# PowerSupply.net
KiCad netlist of a schematic drawn in Altium Designer
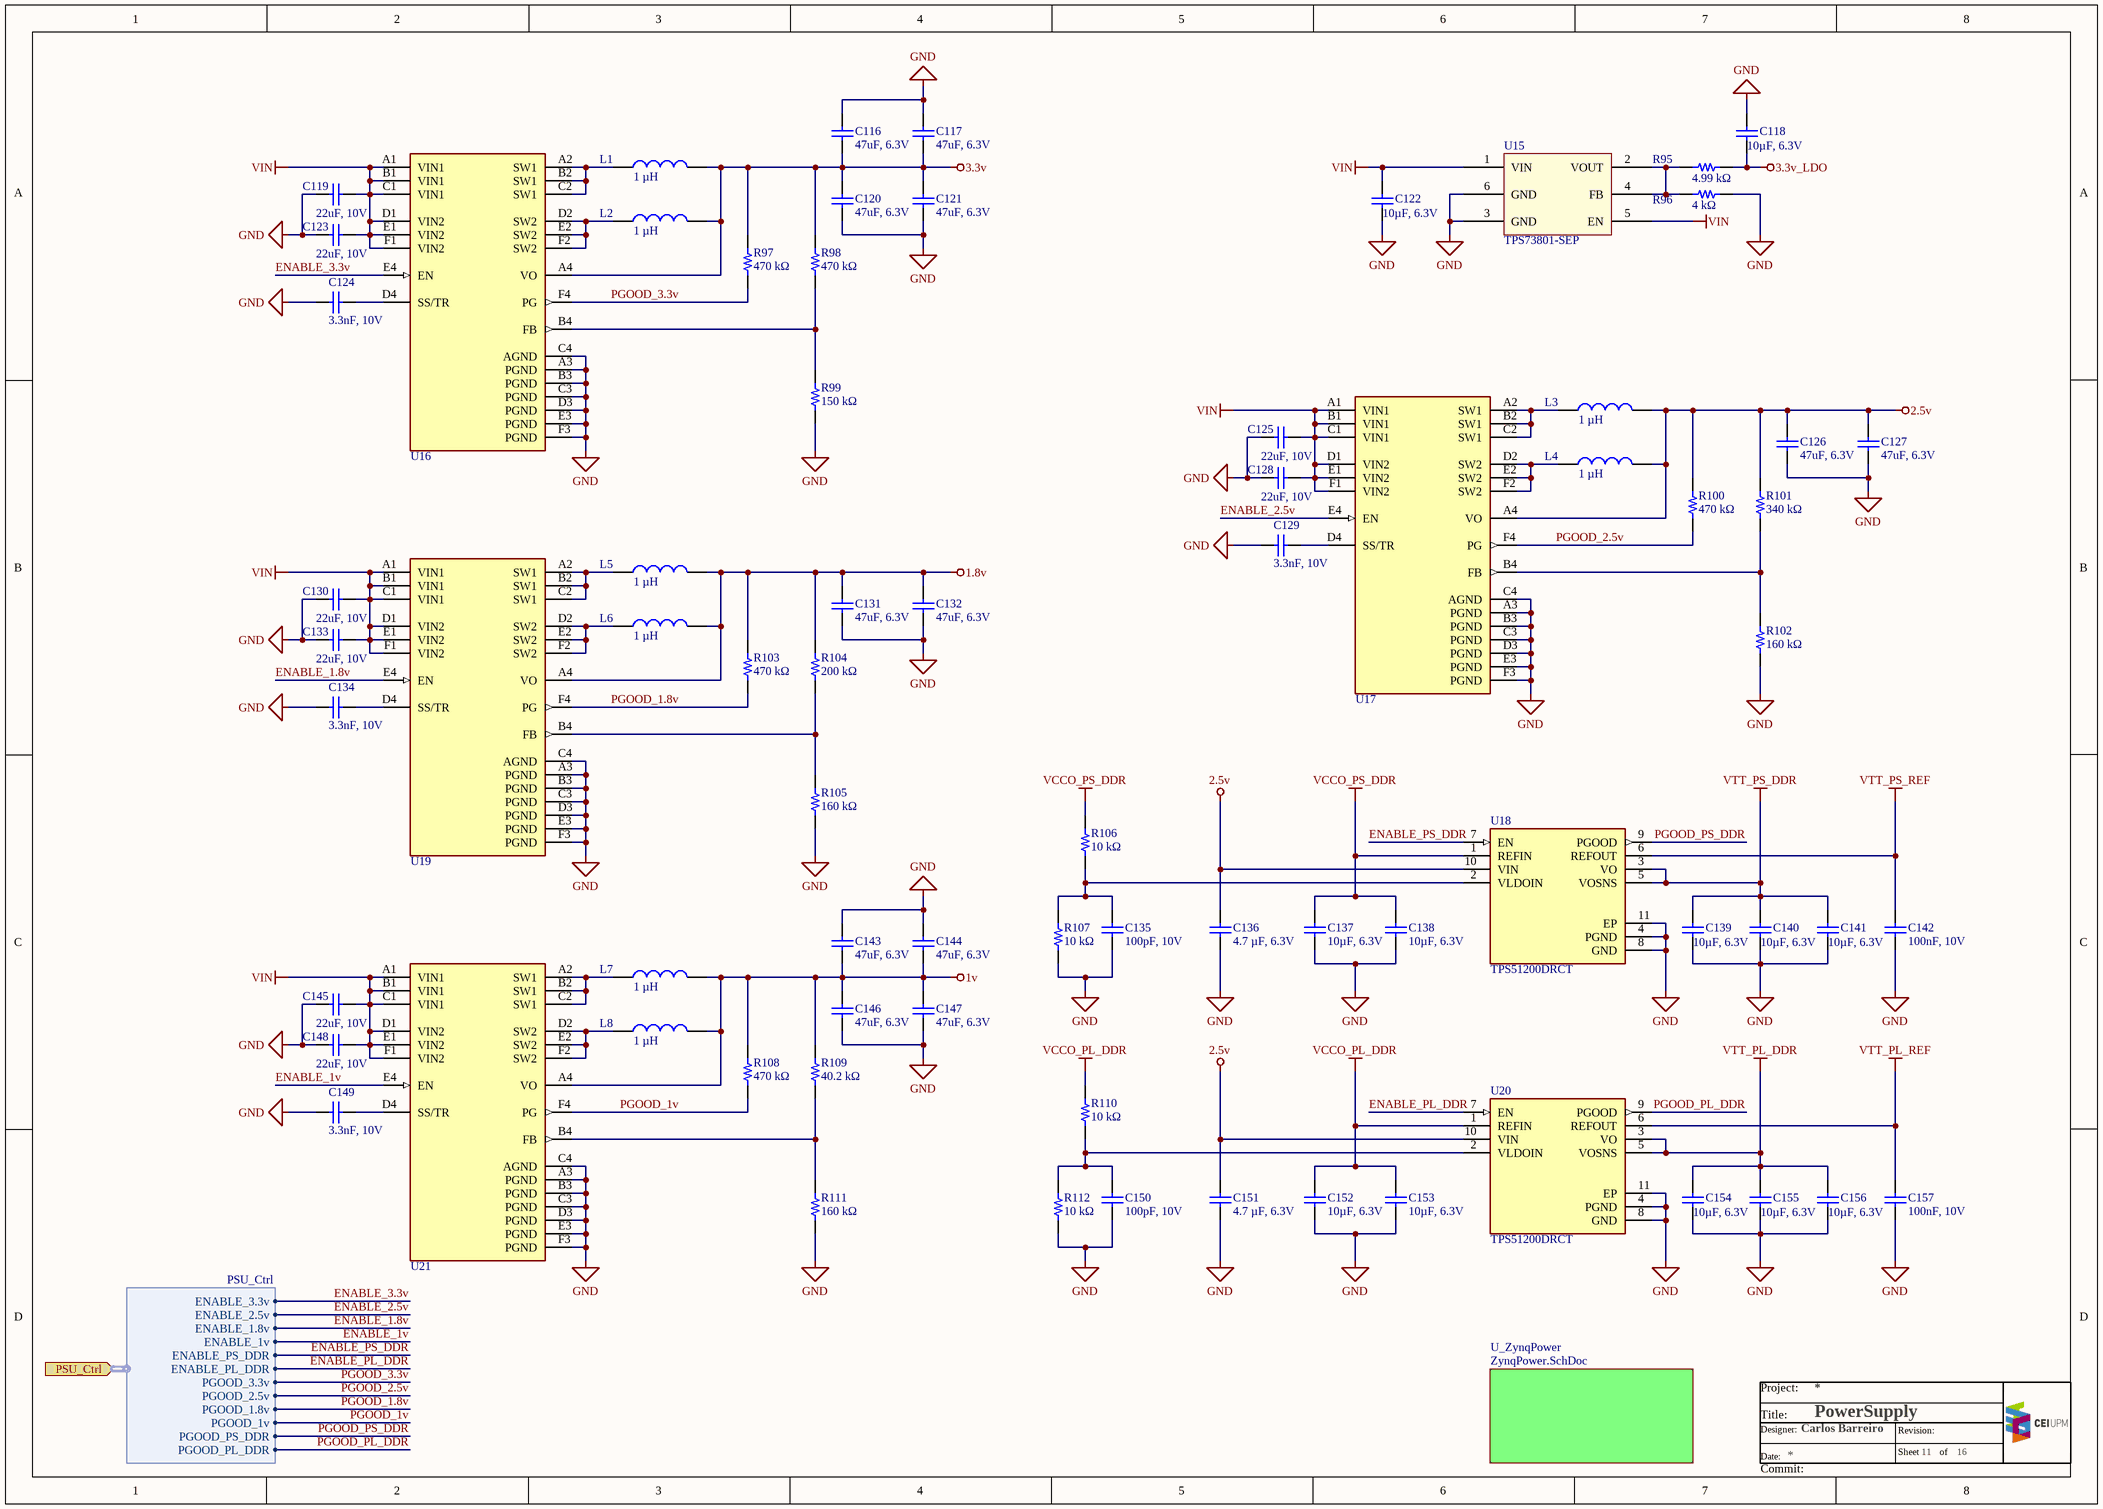
[diagram p0: PowerSupply.SchDoc]

(export (version "E")
  (design (tool "Eeschema 10.0.6"))
  (components
    (comp (ref "C116")
      (value "47uF, 6.3V")
      (footprint "WURTH_WCAP-CSGP_0805_H=1.25mm")
      (description "WCAP-CSGP Multilayer Ceramic Chip Capacitor, General Purpose, size 0805, X5R, 47uF, 6.3V")
      (fields
        (field (name "MANUFACTURER PART NUMBER") "885012107006")
        (field (name "MANUFACTURER") "Wurth Elektronik")
      )
      (libsource (lib "SpaceVNX") (part "885012107006"))
    )
    (comp (ref "C117")
      (value "47uF, 6.3V")
      (footprint "WURTH_WCAP-CSGP_0805_H=1.25mm")
      (description "WCAP-CSGP Multilayer Ceramic Chip Capacitor, General Purpose, size 0805, X5R, 47uF, 6.3V")
      (fields
        (field (name "MANUFACTURER PART NUMBER") "885012107006")
        (field (name "MANUFACTURER") "Wurth Elektronik")
      )
      (libsource (lib "SpaceVNX") (part "885012107006"))
    )
    (comp (ref "C118")
      (value "10µF, 6.3V")
      (footprint "WURTH_WCAP-CSGP_0402")
      (description "WCAP-CSGP Multilayer Ceramic Chip Capacitor, General Purpose, size 0402, X5R, 10uF, 6.3V")
      (fields
        (field (name "MANUFACTURER PART NUMBER") "885012105020")
        (field (name "MANUFACTURER") "Wurth Elektronik")
      )
      (libsource (lib "SpaceVNX") (part "885012105020"))
    )
    (comp (ref "C119")
      (value "22uF, 10V")
      (footprint "WURTH_WCAP-CSGP_0805_H=1.25mm")
      (description "WCAP-CSGP Multilayer Ceramic Chip Capacitor, General Purpose, size 0805, X5R, 22uF, 10V")
      (fields
        (field (name "MANUFACTURER PART NUMBER") "885012107011")
        (field (name "MANUFACTURER") "Wurth Elektronik")
      )
      (libsource (lib "SpaceVNX") (part "885012107011"))
    )
    (comp (ref "C120")
      (value "47uF, 6.3V")
      (footprint "WURTH_WCAP-CSGP_0805_H=1.25mm")
      (description "WCAP-CSGP Multilayer Ceramic Chip Capacitor, General Purpose, size 0805, X5R, 47uF, 6.3V")
      (fields
        (field (name "MANUFACTURER PART NUMBER") "885012107006")
        (field (name "MANUFACTURER") "Wurth Elektronik")
      )
      (libsource (lib "SpaceVNX") (part "885012107006"))
    )
    (comp (ref "C121")
      (value "47uF, 6.3V")
      (footprint "WURTH_WCAP-CSGP_0805_H=1.25mm")
      (description "WCAP-CSGP Multilayer Ceramic Chip Capacitor, General Purpose, size 0805, X5R, 47uF, 6.3V")
      (fields
        (field (name "MANUFACTURER PART NUMBER") "885012107006")
        (field (name "MANUFACTURER") "Wurth Elektronik")
      )
      (libsource (lib "SpaceVNX") (part "885012107006"))
    )
    (comp (ref "C122")
      (value "10µF, 6.3V")
      (footprint "WURTH_WCAP-CSGP_0402")
      (description "WCAP-CSGP Multilayer Ceramic Chip Capacitor, General Purpose, size 0402, X5R, 10uF, 6.3V")
      (fields
        (field (name "MANUFACTURER PART NUMBER") "885012105020")
        (field (name "MANUFACTURER") "Wurth Elektronik")
      )
      (libsource (lib "SpaceVNX") (part "885012105020"))
    )
    (comp (ref "C123")
      (value "22uF, 10V")
      (footprint "WURTH_WCAP-CSGP_0805_H=1.25mm")
      (description "WCAP-CSGP Multilayer Ceramic Chip Capacitor, General Purpose, size 0805, X5R, 22uF, 10V")
      (fields
        (field (name "MANUFACTURER PART NUMBER") "885012107011")
        (field (name "MANUFACTURER") "Wurth Elektronik")
      )
      (libsource (lib "SpaceVNX") (part "885012107011"))
    )
    (comp (ref "C124")
      (value "3.3nF, 10V")
      (footprint "WURTH_WCAP-CSGP_0402")
      (description "WCAP-CSGP Multilayer Ceramic Chip Capacitor, General Purpose, size 0402, X7R, 3.3nF, 10V")
      (fields
        (field (name "MANUFACTURER PART NUMBER") "885012205009")
        (field (name "MANUFACTURER") "Wurth Elektronik")
      )
      (libsource (lib "SpaceVNX") (part "885012205009"))
    )
    (comp (ref "C125")
      (value "22uF, 10V")
      (footprint "WURTH_WCAP-CSGP_0805_H=1.25mm")
      (description "WCAP-CSGP Multilayer Ceramic Chip Capacitor, General Purpose, size 0805, X5R, 22uF, 10V")
      (fields
        (field (name "MANUFACTURER PART NUMBER") "885012107011")
        (field (name "MANUFACTURER") "Wurth Elektronik")
      )
      (libsource (lib "SpaceVNX") (part "885012107011"))
    )
    (comp (ref "C126")
      (value "47uF, 6.3V")
      (footprint "WURTH_WCAP-CSGP_0805_H=1.25mm")
      (description "WCAP-CSGP Multilayer Ceramic Chip Capacitor, General Purpose, size 0805, X5R, 47uF, 6.3V")
      (fields
        (field (name "MANUFACTURER PART NUMBER") "885012107006")
        (field (name "MANUFACTURER") "Wurth Elektronik")
      )
      (libsource (lib "SpaceVNX") (part "885012107006"))
    )
    (comp (ref "C127")
      (value "47uF, 6.3V")
      (footprint "WURTH_WCAP-CSGP_0805_H=1.25mm")
      (description "WCAP-CSGP Multilayer Ceramic Chip Capacitor, General Purpose, size 0805, X5R, 47uF, 6.3V")
      (fields
        (field (name "MANUFACTURER PART NUMBER") "885012107006")
        (field (name "MANUFACTURER") "Wurth Elektronik")
      )
      (libsource (lib "SpaceVNX") (part "885012107006"))
    )
    (comp (ref "C128")
      (value "22uF, 10V")
      (footprint "WURTH_WCAP-CSGP_0805_H=1.25mm")
      (description "WCAP-CSGP Multilayer Ceramic Chip Capacitor, General Purpose, size 0805, X5R, 22uF, 10V")
      (fields
        (field (name "MANUFACTURER PART NUMBER") "885012107011")
        (field (name "MANUFACTURER") "Wurth Elektronik")
      )
      (libsource (lib "SpaceVNX") (part "885012107011"))
    )
    (comp (ref "C129")
      (value "3.3nF, 10V")
      (footprint "WURTH_WCAP-CSGP_0402")
      (description "WCAP-CSGP Multilayer Ceramic Chip Capacitor, General Purpose, size 0402, X7R, 3.3nF, 10V")
      (fields
        (field (name "MANUFACTURER PART NUMBER") "885012205009")
        (field (name "MANUFACTURER") "Wurth Elektronik")
      )
      (libsource (lib "SpaceVNX") (part "885012205009"))
    )
    (comp (ref "C130")
      (value "22uF, 10V")
      (footprint "WURTH_WCAP-CSGP_0805_H=1.25mm")
      (description "WCAP-CSGP Multilayer Ceramic Chip Capacitor, General Purpose, size 0805, X5R, 22uF, 10V")
      (fields
        (field (name "MANUFACTURER PART NUMBER") "885012107011")
        (field (name "MANUFACTURER") "Wurth Elektronik")
      )
      (libsource (lib "SpaceVNX") (part "885012107011"))
    )
    (comp (ref "C131")
      (value "47uF, 6.3V")
      (footprint "WURTH_WCAP-CSGP_0805_H=1.25mm")
      (description "WCAP-CSGP Multilayer Ceramic Chip Capacitor, General Purpose, size 0805, X5R, 47uF, 6.3V")
      (fields
        (field (name "MANUFACTURER PART NUMBER") "885012107006")
        (field (name "MANUFACTURER") "Wurth Elektronik")
      )
      (libsource (lib "SpaceVNX") (part "885012107006"))
    )
    (comp (ref "C132")
      (value "47uF, 6.3V")
      (footprint "WURTH_WCAP-CSGP_0805_H=1.25mm")
      (description "WCAP-CSGP Multilayer Ceramic Chip Capacitor, General Purpose, size 0805, X5R, 47uF, 6.3V")
      (fields
        (field (name "MANUFACTURER PART NUMBER") "885012107006")
        (field (name "MANUFACTURER") "Wurth Elektronik")
      )
      (libsource (lib "SpaceVNX") (part "885012107006"))
    )
    (comp (ref "C133")
      (value "22uF, 10V")
      (footprint "WURTH_WCAP-CSGP_0805_H=1.25mm")
      (description "WCAP-CSGP Multilayer Ceramic Chip Capacitor, General Purpose, size 0805, X5R, 22uF, 10V")
      (fields
        (field (name "MANUFACTURER PART NUMBER") "885012107011")
        (field (name "MANUFACTURER") "Wurth Elektronik")
      )
      (libsource (lib "SpaceVNX") (part "885012107011"))
    )
    (comp (ref "C134")
      (value "3.3nF, 10V")
      (footprint "WURTH_WCAP-CSGP_0402")
      (description "WCAP-CSGP Multilayer Ceramic Chip Capacitor, General Purpose, size 0402, X7R, 3.3nF, 10V")
      (fields
        (field (name "MANUFACTURER PART NUMBER") "885012205009")
        (field (name "MANUFACTURER") "Wurth Elektronik")
      )
      (libsource (lib "SpaceVNX") (part "885012205009"))
    )
    (comp (ref "C135")
      (value "100pF, 10V")
      (footprint "WURTH_WCAP-CSGP_0402")
      (description "WCAP-CSGP Multilayer Ceramic Chip Capacitor, General Purpose, size 0402, NP0, 100pF, 10V")
      (fields
        (field (name "MANUFACTURER PART NUMBER") "885012005013")
        (field (name "MANUFACTURER") "Wurth Elektronik")
      )
      (libsource (lib "SpaceVNX") (part "885012005013"))
    )
    (comp (ref "C136")
      (value "4.7 µF, 6.3V")
      (footprint "WURTH_WCAP-CSGP_0402")
      (description "Multilayer Ceramic Capacitors MLCC, size 0402, X5R, 4.7 µF, 6.3V")
      (fields
        (field (name "MANUFACTURER PART NUMBER") "GRM155C80J475MEAAD")
        (field (name "MANUFACTURER") "Murata")
      )
      (libsource (lib "SpaceVNX") (part "GRM155C80J475MEAAD"))
    )
    (comp (ref "C137")
      (value "10µF, 6.3V")
      (footprint "WURTH_WCAP-CSGP_0402")
      (description "WCAP-CSGP Multilayer Ceramic Chip Capacitor, General Purpose, size 0402, X5R, 10uF, 6.3V")
      (fields
        (field (name "MANUFACTURER PART NUMBER") "885012105020")
        (field (name "MANUFACTURER") "Wurth Elektronik")
      )
      (libsource (lib "SpaceVNX") (part "885012105020"))
    )
    (comp (ref "C138")
      (value "10µF, 6.3V")
      (footprint "WURTH_WCAP-CSGP_0402")
      (description "WCAP-CSGP Multilayer Ceramic Chip Capacitor, General Purpose, size 0402, X5R, 10uF, 6.3V")
      (fields
        (field (name "MANUFACTURER PART NUMBER") "885012105020")
        (field (name "MANUFACTURER") "Wurth Elektronik")
      )
      (libsource (lib "SpaceVNX") (part "885012105020"))
    )
    (comp (ref "C139")
      (value "10µF, 6.3V")
      (footprint "WURTH_WCAP-CSGP_0402")
      (description "WCAP-CSGP Multilayer Ceramic Chip Capacitor, General Purpose, size 0402, X5R, 10uF, 6.3V")
      (fields
        (field (name "MANUFACTURER PART NUMBER") "885012105020")
        (field (name "MANUFACTURER") "Wurth Elektronik")
      )
      (libsource (lib "SpaceVNX") (part "885012105020"))
    )
    (comp (ref "C140")
      (value "10µF, 6.3V")
      (footprint "WURTH_WCAP-CSGP_0402")
      (description "WCAP-CSGP Multilayer Ceramic Chip Capacitor, General Purpose, size 0402, X5R, 10uF, 6.3V")
      (fields
        (field (name "MANUFACTURER PART NUMBER") "885012105020")
        (field (name "MANUFACTURER") "Wurth Elektronik")
      )
      (libsource (lib "SpaceVNX") (part "885012105020"))
    )
    (comp (ref "C141")
      (value "10µF, 6.3V")
      (footprint "WURTH_WCAP-CSGP_0402")
      (description "WCAP-CSGP Multilayer Ceramic Chip Capacitor, General Purpose, size 0402, X5R, 10uF, 6.3V")
      (fields
        (field (name "MANUFACTURER PART NUMBER") "885012105020")
        (field (name "MANUFACTURER") "Wurth Elektronik")
      )
      (libsource (lib "SpaceVNX") (part "885012105020"))
    )
    (comp (ref "C142")
      (value "100nF, 10V")
      (footprint "WURTH_WCAP-CSGP_0402")
      (description "WCAP-CSGP Multilayer Ceramic Chip Capacitor, General Purpose, size 0402, X7R, 100nF, 10V")
      (fields
        (field (name "MANUFACTURER PART NUMBER") "885012205018")
        (field (name "MANUFACTURER") "Wurth Elektronik")
      )
      (libsource (lib "SpaceVNX") (part "885012205018"))
    )
    (comp (ref "C143")
      (value "47uF, 6.3V")
      (footprint "WURTH_WCAP-CSGP_0805_H=1.25mm")
      (description "WCAP-CSGP Multilayer Ceramic Chip Capacitor, General Purpose, size 0805, X5R, 47uF, 6.3V")
      (fields
        (field (name "MANUFACTURER PART NUMBER") "885012107006")
        (field (name "MANUFACTURER") "Wurth Elektronik")
      )
      (libsource (lib "SpaceVNX") (part "885012107006"))
    )
    (comp (ref "C144")
      (value "47uF, 6.3V")
      (footprint "WURTH_WCAP-CSGP_0805_H=1.25mm")
      (description "WCAP-CSGP Multilayer Ceramic Chip Capacitor, General Purpose, size 0805, X5R, 47uF, 6.3V")
      (fields
        (field (name "MANUFACTURER PART NUMBER") "885012107006")
        (field (name "MANUFACTURER") "Wurth Elektronik")
      )
      (libsource (lib "SpaceVNX") (part "885012107006"))
    )
    (comp (ref "C145")
      (value "22uF, 10V")
      (footprint "WURTH_WCAP-CSGP_0805_H=1.25mm")
      (description "WCAP-CSGP Multilayer Ceramic Chip Capacitor, General Purpose, size 0805, X5R, 22uF, 10V")
      (fields
        (field (name "MANUFACTURER PART NUMBER") "885012107011")
        (field (name "MANUFACTURER") "Wurth Elektronik")
      )
      (libsource (lib "SpaceVNX") (part "885012107011"))
    )
    (comp (ref "C146")
      (value "47uF, 6.3V")
      (footprint "WURTH_WCAP-CSGP_0805_H=1.25mm")
      (description "WCAP-CSGP Multilayer Ceramic Chip Capacitor, General Purpose, size 0805, X5R, 47uF, 6.3V")
      (fields
        (field (name "MANUFACTURER PART NUMBER") "885012107006")
        (field (name "MANUFACTURER") "Wurth Elektronik")
      )
      (libsource (lib "SpaceVNX") (part "885012107006"))
    )
    (comp (ref "C147")
      (value "47uF, 6.3V")
      (footprint "WURTH_WCAP-CSGP_0805_H=1.25mm")
      (description "WCAP-CSGP Multilayer Ceramic Chip Capacitor, General Purpose, size 0805, X5R, 47uF, 6.3V")
      (fields
        (field (name "MANUFACTURER PART NUMBER") "885012107006")
        (field (name "MANUFACTURER") "Wurth Elektronik")
      )
      (libsource (lib "SpaceVNX") (part "885012107006"))
    )
    (comp (ref "C148")
      (value "22uF, 10V")
      (footprint "WURTH_WCAP-CSGP_0805_H=1.25mm")
      (description "WCAP-CSGP Multilayer Ceramic Chip Capacitor, General Purpose, size 0805, X5R, 22uF, 10V")
      (fields
        (field (name "MANUFACTURER PART NUMBER") "885012107011")
        (field (name "MANUFACTURER") "Wurth Elektronik")
      )
      (libsource (lib "SpaceVNX") (part "885012107011"))
    )
    (comp (ref "C149")
      (value "3.3nF, 10V")
      (footprint "WURTH_WCAP-CSGP_0402")
      (description "WCAP-CSGP Multilayer Ceramic Chip Capacitor, General Purpose, size 0402, X7R, 3.3nF, 10V")
      (fields
        (field (name "MANUFACTURER PART NUMBER") "885012205009")
        (field (name "MANUFACTURER") "Wurth Elektronik")
      )
      (libsource (lib "SpaceVNX") (part "885012205009"))
    )
    (comp (ref "C150")
      (value "100pF, 10V")
      (footprint "WURTH_WCAP-CSGP_0402")
      (description "WCAP-CSGP Multilayer Ceramic Chip Capacitor, General Purpose, size 0402, NP0, 100pF, 10V")
      (fields
        (field (name "MANUFACTURER PART NUMBER") "885012005013")
        (field (name "MANUFACTURER") "Wurth Elektronik")
      )
      (libsource (lib "SpaceVNX") (part "885012005013"))
    )
    (comp (ref "C151")
      (value "4.7 µF, 6.3V")
      (footprint "WURTH_WCAP-CSGP_0402")
      (description "Multilayer Ceramic Capacitors MLCC, size 0402, X5R, 4.7 µF, 6.3V")
      (fields
        (field (name "MANUFACTURER PART NUMBER") "GRM155C80J475MEAAD")
        (field (name "MANUFACTURER") "Murata")
      )
      (libsource (lib "SpaceVNX") (part "GRM155C80J475MEAAD"))
    )
    (comp (ref "C152")
      (value "10µF, 6.3V")
      (footprint "WURTH_WCAP-CSGP_0402")
      (description "WCAP-CSGP Multilayer Ceramic Chip Capacitor, General Purpose, size 0402, X5R, 10uF, 6.3V")
      (fields
        (field (name "MANUFACTURER PART NUMBER") "885012105020")
        (field (name "MANUFACTURER") "Wurth Elektronik")
      )
      (libsource (lib "SpaceVNX") (part "885012105020"))
    )
    (comp (ref "C153")
      (value "10µF, 6.3V")
      (footprint "WURTH_WCAP-CSGP_0402")
      (description "WCAP-CSGP Multilayer Ceramic Chip Capacitor, General Purpose, size 0402, X5R, 10uF, 6.3V")
      (fields
        (field (name "MANUFACTURER PART NUMBER") "885012105020")
        (field (name "MANUFACTURER") "Wurth Elektronik")
      )
      (libsource (lib "SpaceVNX") (part "885012105020"))
    )
    (comp (ref "C154")
      (value "10µF, 6.3V")
      (footprint "WURTH_WCAP-CSGP_0402")
      (description "WCAP-CSGP Multilayer Ceramic Chip Capacitor, General Purpose, size 0402, X5R, 10uF, 6.3V")
      (fields
        (field (name "MANUFACTURER PART NUMBER") "885012105020")
        (field (name "MANUFACTURER") "Wurth Elektronik")
      )
      (libsource (lib "SpaceVNX") (part "885012105020"))
    )
    (comp (ref "C155")
      (value "10µF, 6.3V")
      (footprint "WURTH_WCAP-CSGP_0402")
      (description "WCAP-CSGP Multilayer Ceramic Chip Capacitor, General Purpose, size 0402, X5R, 10uF, 6.3V")
      (fields
        (field (name "MANUFACTURER PART NUMBER") "885012105020")
        (field (name "MANUFACTURER") "Wurth Elektronik")
      )
      (libsource (lib "SpaceVNX") (part "885012105020"))
    )
    (comp (ref "C156")
      (value "10µF, 6.3V")
      (footprint "WURTH_WCAP-CSGP_0402")
      (description "WCAP-CSGP Multilayer Ceramic Chip Capacitor, General Purpose, size 0402, X5R, 10uF, 6.3V")
      (fields
        (field (name "MANUFACTURER PART NUMBER") "885012105020")
        (field (name "MANUFACTURER") "Wurth Elektronik")
      )
      (libsource (lib "SpaceVNX") (part "885012105020"))
    )
    (comp (ref "C157")
      (value "100nF, 10V")
      (footprint "WURTH_WCAP-CSGP_0402")
      (description "WCAP-CSGP Multilayer Ceramic Chip Capacitor, General Purpose, size 0402, X7R, 100nF, 10V")
      (fields
        (field (name "MANUFACTURER PART NUMBER") "885012205018")
        (field (name "MANUFACTURER") "Wurth Elektronik")
      )
      (libsource (lib "SpaceVNX") (part "885012205018"))
    )
    (comp (ref "L1")
      (value "1 µH")
      (footprint "Murata_LQH2HPN_JR")
      (description "Wire Wound Ferrite Inductor")
      (fields (field (name "MANUFACTURER") "Murata"))
      (libsource (lib "SpaceVNX") (part "LQH2HPN1R0NJR"))
    )
    (comp (ref "L2")
      (value "1 µH")
      (footprint "Murata_LQH2HPN_JR")
      (description "Wire Wound Ferrite Inductor")
      (fields (field (name "MANUFACTURER") "Murata"))
      (libsource (lib "SpaceVNX") (part "LQH2HPN1R0NJR"))
    )
    (comp (ref "L3")
      (value "1 µH")
      (footprint "Murata_LQH2HPN_JR")
      (description "Wire Wound Ferrite Inductor")
      (fields (field (name "MANUFACTURER") "Murata"))
      (libsource (lib "SpaceVNX") (part "LQH2HPN1R0NJR"))
    )
    (comp (ref "L4")
      (value "1 µH")
      (footprint "Murata_LQH2HPN_JR")
      (description "Wire Wound Ferrite Inductor")
      (fields (field (name "MANUFACTURER") "Murata"))
      (libsource (lib "SpaceVNX") (part "LQH2HPN1R0NJR"))
    )
    (comp (ref "L5")
      (value "1 µH")
      (footprint "Murata_LQH2HPN_JR")
      (description "Wire Wound Ferrite Inductor")
      (fields (field (name "MANUFACTURER") "Murata"))
      (libsource (lib "SpaceVNX") (part "LQH2HPN1R0NJR"))
    )
    (comp (ref "L6")
      (value "1 µH")
      (footprint "Murata_LQH2HPN_JR")
      (description "Wire Wound Ferrite Inductor")
      (fields (field (name "MANUFACTURER") "Murata"))
      (libsource (lib "SpaceVNX") (part "LQH2HPN1R0NJR"))
    )
    (comp (ref "L7")
      (value "1 µH")
      (footprint "Murata_LQH2HPN_JR")
      (description "Wire Wound Ferrite Inductor")
      (fields (field (name "MANUFACTURER") "Murata"))
      (libsource (lib "SpaceVNX") (part "LQH2HPN1R0NJR"))
    )
    (comp (ref "L8")
      (value "1 µH")
      (footprint "Murata_LQH2HPN_JR")
      (description "Wire Wound Ferrite Inductor")
      (fields (field (name "MANUFACTURER") "Murata"))
      (libsource (lib "SpaceVNX") (part "LQH2HPN1R0NJR"))
    )
    (comp (ref "R95")
      (value "4.99 kΩ")
      (footprint "PANASONIC_ERJ2G_0402")
      (description "General Purpose Thick Film Chip Resistors")
      (fields (field (name "MANUFACTURER") "Panasonic"))
      (libsource (lib "SpaceVNX") (part "ERJ2RKF4991X"))
    )
    (comp (ref "R96")
      (value "4 kΩ")
      (footprint "PANASONIC_ERJ2G_0402")
      (description "General Purpose Thick Film Chip Resistors")
      (fields (field (name "MANUFACTURER") "Panasonic"))
      (libsource (lib "SpaceVNX") (part "ERJ2RKF4021X"))
    )
    (comp (ref "R97")
      (value "470 kΩ")
      (footprint "PANASONIC_ERJ2G_0402")
      (description "General Purpose Thick Film Chip Resistors")
      (fields (field (name "MANUFACTURER") "Panasonic"))
      (libsource (lib "SpaceVNX") (part "ERJ2RKF4703X"))
    )
    (comp (ref "R98")
      (value "470 kΩ")
      (footprint "PANASONIC_ERJ2G_0402")
      (description "General Purpose Thick Film Chip Resistors")
      (fields (field (name "MANUFACTURER") "Panasonic"))
      (libsource (lib "SpaceVNX") (part "ERJ2RKF4703X"))
    )
    (comp (ref "R99")
      (value "150 kΩ")
      (footprint "PANASONIC_ERJ2G_0402")
      (description "General Purpose Thick Film Chip Resistors")
      (fields (field (name "MANUFACTURER") "Panasonic"))
      (libsource (lib "SpaceVNX") (part "ERJ2RKF1503X"))
    )
    (comp (ref "R100")
      (value "470 kΩ")
      (footprint "PANASONIC_ERJ2G_0402")
      (description "General Purpose Thick Film Chip Resistors")
      (fields (field (name "MANUFACTURER") "Panasonic"))
      (libsource (lib "SpaceVNX") (part "ERJ2RKF4703X"))
    )
    (comp (ref "R101")
      (value "340 kΩ")
      (footprint "PANASONIC_ERJ2G_0402")
      (description "General Purpose Thick Film Chip Resistors")
      (fields (field (name "MANUFACTURER") "Panasonic"))
      (libsource (lib "SpaceVNX") (part "ERJ2RKF3403X"))
    )
    (comp (ref "R102")
      (value "160 kΩ")
      (footprint "PANASONIC_ERJ2G_0402")
      (description "General Purpose Thick Film Chip Resistors")
      (fields (field (name "MANUFACTURER") "Panasonic"))
      (libsource (lib "SpaceVNX") (part "ERJ2RKF1603X"))
    )
    (comp (ref "R103")
      (value "470 kΩ")
      (footprint "PANASONIC_ERJ2G_0402")
      (description "General Purpose Thick Film Chip Resistors")
      (fields (field (name "MANUFACTURER") "Panasonic"))
      (libsource (lib "SpaceVNX") (part "ERJ2RKF4703X"))
    )
    (comp (ref "R104")
      (value "200 kΩ")
      (footprint "PANASONIC_ERJ2G_0402")
      (description "General Purpose Thick Film Chip Resistors")
      (fields (field (name "MANUFACTURER") "Panasonic"))
      (libsource (lib "SpaceVNX") (part "ERJ2RKF2003X"))
    )
    (comp (ref "R105")
      (value "160 kΩ")
      (footprint "PANASONIC_ERJ2G_0402")
      (description "General Purpose Thick Film Chip Resistors")
      (fields (field (name "MANUFACTURER") "Panasonic"))
      (libsource (lib "SpaceVNX") (part "ERJ2RKF1603X"))
    )
    (comp (ref "R106")
      (value "10 kΩ")
      (footprint "PANASONIC_ERJ2G_0402")
      (description "General Purpose Thick Film Chip Resistors")
      (fields (field (name "MANUFACTURER") "Panasonic"))
      (libsource (lib "SpaceVNX") (part "ERJ2RKF1002X"))
    )
    (comp (ref "R107")
      (value "10 kΩ")
      (footprint "PANASONIC_ERJ2G_0402")
      (description "General Purpose Thick Film Chip Resistors")
      (fields (field (name "MANUFACTURER") "Panasonic"))
      (libsource (lib "SpaceVNX") (part "ERJ2RKF1002X"))
    )
    (comp (ref "R108")
      (value "470 kΩ")
      (footprint "PANASONIC_ERJ2G_0402")
      (description "General Purpose Thick Film Chip Resistors")
      (fields (field (name "MANUFACTURER") "Panasonic"))
      (libsource (lib "SpaceVNX") (part "ERJ2RKF4703X"))
    )
    (comp (ref "R109")
      (value "40.2 kΩ")
      (footprint "PANASONIC_ERJ2G_0402")
      (description "General Purpose Thick Film Chip Resistors")
      (fields (field (name "MANUFACTURER") "Panasonic"))
      (libsource (lib "SpaceVNX") (part "ERJ2RKF4022X"))
    )
    (comp (ref "R110")
      (value "10 kΩ")
      (footprint "PANASONIC_ERJ2G_0402")
      (description "General Purpose Thick Film Chip Resistors")
      (fields (field (name "MANUFACTURER") "Panasonic"))
      (libsource (lib "SpaceVNX") (part "ERJ2RKF1002X"))
    )
    (comp (ref "R111")
      (value "160 kΩ")
      (footprint "PANASONIC_ERJ2G_0402")
      (description "General Purpose Thick Film Chip Resistors")
      (fields (field (name "MANUFACTURER") "Panasonic"))
      (libsource (lib "SpaceVNX") (part "ERJ2RKF1603X"))
    )
    (comp (ref "R112")
      (value "10 kΩ")
      (footprint "PANASONIC_ERJ2G_0402")
      (description "General Purpose Thick Film Chip Resistors")
      (fields (field (name "MANUFACTURER") "Panasonic"))
      (libsource (lib "SpaceVNX") (part "ERJ2RKF1002X"))
    )
    (comp (ref "U15")
      (value "TPS73801-SEP")
      (footprint "TEXAS_SOT223DCQ")
      (description "Radiation-hardened, 2.2-V to 20-V, 1-A low-noise adjustable output LDO in Space Enhanced Plastic")
      (libsource (lib "SpaceVNX") (part "TPS73801-SEP"))
    )
    (comp (ref "U16")
      (value "TPS62180YZFT")
      (footprint "TEXAS_DSBGA24")
      (description "TPS6218x 4-V to 15-V, 6-A, 2-Phase Step-Down Converters")
      (libsource (lib "SpaceVNX") (part "TPS62180YZFT"))
    )
    (comp (ref "U17")
      (value "TPS62180YZFT")
      (footprint "TEXAS_DSBGA24")
      (description "TPS6218x 4-V to 15-V, 6-A, 2-Phase Step-Down Converters")
      (libsource (lib "SpaceVNX") (part "TPS62180YZFT"))
    )
    (comp (ref "U18")
      (value "TPS51200DRCT")
      (footprint "TEXAS_VSON10")
      (fields (field (name "MF") "Texas Instruments"))
      (libsource (lib "SpaceVNX") (part "TPS51200DRCT"))
    )
    (comp (ref "U19")
      (value "TPS62180YZFT")
      (footprint "TEXAS_DSBGA24")
      (description "TPS6218x 4-V to 15-V, 6-A, 2-Phase Step-Down Converters")
      (libsource (lib "SpaceVNX") (part "TPS62180YZFT"))
    )
    (comp (ref "U20")
      (value "TPS51200DRCT")
      (footprint "TEXAS_VSON10")
      (fields (field (name "MF") "Texas Instruments"))
      (libsource (lib "SpaceVNX") (part "TPS51200DRCT"))
    )
    (comp (ref "U21")
      (value "TPS62180YZFT")
      (footprint "TEXAS_DSBGA24")
      (description "TPS6218x 4-V to 15-V, 6-A, 2-Phase Step-Down Converters")
      (libsource (lib "SpaceVNX") (part "TPS62180YZFT"))
    )
  )
  (nets
    (net (code "2") (name "/ENABLE_1.8v") (class "Default")
      (node (ref "U19") (pin "E4") (pinfunction "EN_E4") (pintype "input"))
    )
    (net (code "3") (name "/ENABLE_1v") (class "Default")
      (node (ref "U21") (pin "E4") (pinfunction "EN_E4") (pintype "input"))
    )
    (net (code "4") (name "/ENABLE_2.5v") (class "Default")
      (node (ref "U17") (pin "E4") (pinfunction "EN_E4") (pintype "input"))
    )
    (net (code "5") (name "/ENABLE_3.3v") (class "Default")
      (node (ref "U16") (pin "E4") (pinfunction "EN_E4") (pintype "input"))
    )
    (net (code "6") (name "/ENABLE_PL_DDR") (class "Default")
      (node (ref "U20") (pin "7") (pinfunction "EN_7") (pintype "input"))
    )
    (net (code "7") (name "/ENABLE_PS_DDR") (class "Default")
      (node (ref "U18") (pin "7") (pinfunction "EN_7") (pintype "input"))
    )
    (net (code "8") (name "/PGOOD_1.8v") (class "Default")
      (node (ref "R103") (pin "1") (pinfunction "1_1") (pintype "passive"))
      (node (ref "U19") (pin "F4") (pinfunction "PG_F4") (pintype "output"))
    )
    (net (code "9") (name "/PGOOD_1v") (class "Default")
      (node (ref "R108") (pin "1") (pinfunction "1_1") (pintype "passive"))
      (node (ref "U21") (pin "F4") (pinfunction "PG_F4") (pintype "output"))
    )
    (net (code "10") (name "/PGOOD_2.5v") (class "Default")
      (node (ref "R100") (pin "1") (pinfunction "1_1") (pintype "passive"))
      (node (ref "U17") (pin "F4") (pinfunction "PG_F4") (pintype "output"))
    )
    (net (code "11") (name "/PGOOD_3.3v") (class "Default")
      (node (ref "R97") (pin "1") (pinfunction "1_1") (pintype "passive"))
      (node (ref "U16") (pin "F4") (pinfunction "PG_F4") (pintype "output"))
    )
    (net (code "12") (name "/PGOOD_PL_DDR") (class "Default")
      (node (ref "U20") (pin "9") (pinfunction "PGOOD_9") (pintype "output"))
    )
    (net (code "13") (name "/PGOOD_PS_DDR") (class "Default")
      (node (ref "U18") (pin "9") (pinfunction "PGOOD_9") (pintype "output"))
    )
    (net (code "15") (name "1.8v") (class "Default")
      (node (ref "C131") (pin "2") (pinfunction "2_2") (pintype "passive"))
      (node (ref "C132") (pin "2") (pinfunction "2_2") (pintype "passive"))
      (node (ref "L5") (pin "2") (pinfunction "2_2") (pintype "passive"))
      (node (ref "L6") (pin "2") (pinfunction "2_2") (pintype "passive"))
      (node (ref "R103") (pin "2") (pinfunction "2_2") (pintype "passive"))
      (node (ref "R104") (pin "2") (pinfunction "2_2") (pintype "passive"))
      (node (ref "U19") (pin "A4") (pinfunction "VO_A4") (pintype "power_in"))
    )
    (net (code "16") (name "1v") (class "Default")
      (node (ref "C143") (pin "1") (pinfunction "1_1") (pintype "passive"))
      (node (ref "C144") (pin "1") (pinfunction "1_1") (pintype "passive"))
      (node (ref "C146") (pin "2") (pinfunction "2_2") (pintype "passive"))
      (node (ref "C147") (pin "2") (pinfunction "2_2") (pintype "passive"))
      (node (ref "L7") (pin "2") (pinfunction "2_2") (pintype "passive"))
      (node (ref "L8") (pin "2") (pinfunction "2_2") (pintype "passive"))
      (node (ref "R108") (pin "2") (pinfunction "2_2") (pintype "passive"))
      (node (ref "R109") (pin "2") (pinfunction "2_2") (pintype "passive"))
      (node (ref "U21") (pin "A4") (pinfunction "VO_A4") (pintype "power_in"))
    )
    (net (code "17") (name "2.5v") (class "Default")
      (node (ref "C126") (pin "2") (pinfunction "2_2") (pintype "passive"))
      (node (ref "C127") (pin "2") (pinfunction "2_2") (pintype "passive"))
      (node (ref "C136") (pin "2") (pinfunction "2_2") (pintype "passive"))
      (node (ref "C151") (pin "2") (pinfunction "2_2") (pintype "passive"))
      (node (ref "L3") (pin "2") (pinfunction "2_2") (pintype "passive"))
      (node (ref "L4") (pin "2") (pinfunction "2_2") (pintype "passive"))
      (node (ref "R100") (pin "2") (pinfunction "2_2") (pintype "passive"))
      (node (ref "R101") (pin "2") (pinfunction "2_2") (pintype "passive"))
      (node (ref "U17") (pin "A4") (pinfunction "VO_A4") (pintype "power_in"))
      (node (ref "U18") (pin "10") (pinfunction "VIN_10") (pintype "passive"))
      (node (ref "U20") (pin "10") (pinfunction "VIN_10") (pintype "passive"))
    )
    (net (code "18") (name "3.3v") (class "Default")
      (node (ref "C116") (pin "1") (pinfunction "1_1") (pintype "passive"))
      (node (ref "C117") (pin "1") (pinfunction "1_1") (pintype "passive"))
      (node (ref "C120") (pin "2") (pinfunction "2_2") (pintype "passive"))
      (node (ref "C121") (pin "2") (pinfunction "2_2") (pintype "passive"))
      (node (ref "L1") (pin "2") (pinfunction "2_2") (pintype "passive"))
      (node (ref "L2") (pin "2") (pinfunction "2_2") (pintype "passive"))
      (node (ref "R97") (pin "2") (pinfunction "2_2") (pintype "passive"))
      (node (ref "R98") (pin "2") (pinfunction "2_2") (pintype "passive"))
      (node (ref "U16") (pin "A4") (pinfunction "VO_A4") (pintype "power_in"))
    )
    (net (code "19") (name "3.3v_LDO") (class "Default")
      (node (ref "C118") (pin "1") (pinfunction "1_1") (pintype "passive"))
      (node (ref "R95") (pin "2") (pinfunction "2_2") (pintype "passive"))
    )
    (net (code "20") (name "GND") (class "Default")
      (node (ref "C116") (pin "2") (pinfunction "2_2") (pintype "passive"))
      (node (ref "C117") (pin "2") (pinfunction "2_2") (pintype "passive"))
      (node (ref "C118") (pin "2") (pinfunction "2_2") (pintype "passive"))
      (node (ref "C119") (pin "2") (pinfunction "2_2") (pintype "passive"))
      (node (ref "C120") (pin "1") (pinfunction "1_1") (pintype "passive"))
      (node (ref "C121") (pin "1") (pinfunction "1_1") (pintype "passive"))
      (node (ref "C122") (pin "1") (pinfunction "1_1") (pintype "passive"))
      (node (ref "C123") (pin "2") (pinfunction "2_2") (pintype "passive"))
      (node (ref "C124") (pin "1") (pinfunction "1_1") (pintype "passive"))
      (node (ref "C125") (pin "2") (pinfunction "2_2") (pintype "passive"))
      (node (ref "C126") (pin "1") (pinfunction "1_1") (pintype "passive"))
      (node (ref "C127") (pin "1") (pinfunction "1_1") (pintype "passive"))
      (node (ref "C128") (pin "2") (pinfunction "2_2") (pintype "passive"))
      (node (ref "C129") (pin "1") (pinfunction "1_1") (pintype "passive"))
      (node (ref "C130") (pin "2") (pinfunction "2_2") (pintype "passive"))
      (node (ref "C131") (pin "1") (pinfunction "1_1") (pintype "passive"))
      (node (ref "C132") (pin "1") (pinfunction "1_1") (pintype "passive"))
      (node (ref "C133") (pin "2") (pinfunction "2_2") (pintype "passive"))
      (node (ref "C134") (pin "1") (pinfunction "1_1") (pintype "passive"))
      (node (ref "C135") (pin "1") (pinfunction "1_1") (pintype "passive"))
      (node (ref "C136") (pin "1") (pinfunction "1_1") (pintype "passive"))
      (node (ref "C137") (pin "1") (pinfunction "1_1") (pintype "passive"))
      (node (ref "C138") (pin "1") (pinfunction "1_1") (pintype "passive"))
      (node (ref "C139") (pin "1") (pinfunction "1_1") (pintype "passive"))
      (node (ref "C140") (pin "1") (pinfunction "1_1") (pintype "passive"))
      (node (ref "C141") (pin "1") (pinfunction "1_1") (pintype "passive"))
      (node (ref "C142") (pin "1") (pinfunction "1_1") (pintype "passive"))
      (node (ref "C143") (pin "2") (pinfunction "2_2") (pintype "passive"))
      (node (ref "C144") (pin "2") (pinfunction "2_2") (pintype "passive"))
      (node (ref "C145") (pin "2") (pinfunction "2_2") (pintype "passive"))
      (node (ref "C146") (pin "1") (pinfunction "1_1") (pintype "passive"))
      (node (ref "C147") (pin "1") (pinfunction "1_1") (pintype "passive"))
      (node (ref "C148") (pin "2") (pinfunction "2_2") (pintype "passive"))
      (node (ref "C149") (pin "1") (pinfunction "1_1") (pintype "passive"))
      (node (ref "C150") (pin "1") (pinfunction "1_1") (pintype "passive"))
      (node (ref "C151") (pin "1") (pinfunction "1_1") (pintype "passive"))
      (node (ref "C152") (pin "1") (pinfunction "1_1") (pintype "passive"))
      (node (ref "C153") (pin "1") (pinfunction "1_1") (pintype "passive"))
      (node (ref "C154") (pin "1") (pinfunction "1_1") (pintype "passive"))
      (node (ref "C155") (pin "1") (pinfunction "1_1") (pintype "passive"))
      (node (ref "C156") (pin "1") (pinfunction "1_1") (pintype "passive"))
      (node (ref "C157") (pin "1") (pinfunction "1_1") (pintype "passive"))
      (node (ref "R102") (pin "1") (pinfunction "1_1") (pintype "passive"))
      (node (ref "R105") (pin "1") (pinfunction "1_1") (pintype "passive"))
      (node (ref "R107") (pin "1") (pinfunction "1_1") (pintype "passive"))
      (node (ref "R111") (pin "1") (pinfunction "1_1") (pintype "passive"))
      (node (ref "R112") (pin "1") (pinfunction "1_1") (pintype "passive"))
      (node (ref "R96") (pin "2") (pinfunction "2_2") (pintype "passive"))
      (node (ref "R99") (pin "1") (pinfunction "1_1") (pintype "passive"))
      (node (ref "U15") (pin "3") (pinfunction "GND_3") (pintype "passive"))
      (node (ref "U15") (pin "6") (pinfunction "GND_6") (pintype "passive"))
      (node (ref "U16") (pin "A3") (pinfunction "PGND_A3") (pintype "power_in"))
      (node (ref "U16") (pin "B3") (pinfunction "PGND_B3") (pintype "power_in"))
      (node (ref "U16") (pin "C3") (pinfunction "PGND_C3") (pintype "power_in"))
      (node (ref "U16") (pin "C4") (pinfunction "AGND_C4") (pintype "power_in"))
      (node (ref "U16") (pin "D3") (pinfunction "PGND_D3") (pintype "power_in"))
      (node (ref "U16") (pin "E3") (pinfunction "PGND_E3") (pintype "power_in"))
      (node (ref "U16") (pin "F3") (pinfunction "PGND_F3") (pintype "power_in"))
      (node (ref "U17") (pin "A3") (pinfunction "PGND_A3") (pintype "power_in"))
      (node (ref "U17") (pin "B3") (pinfunction "PGND_B3") (pintype "power_in"))
      (node (ref "U17") (pin "C3") (pinfunction "PGND_C3") (pintype "power_in"))
      (node (ref "U17") (pin "C4") (pinfunction "AGND_C4") (pintype "power_in"))
      (node (ref "U17") (pin "D3") (pinfunction "PGND_D3") (pintype "power_in"))
      (node (ref "U17") (pin "E3") (pinfunction "PGND_E3") (pintype "power_in"))
      (node (ref "U17") (pin "F3") (pinfunction "PGND_F3") (pintype "power_in"))
      (node (ref "U18") (pin "11") (pinfunction "EP_11") (pintype "power_in"))
      (node (ref "U18") (pin "4") (pinfunction "PGND_4") (pintype "power_in"))
      (node (ref "U18") (pin "8") (pinfunction "GND_8") (pintype "power_in"))
      (node (ref "U19") (pin "A3") (pinfunction "PGND_A3") (pintype "power_in"))
      (node (ref "U19") (pin "B3") (pinfunction "PGND_B3") (pintype "power_in"))
      (node (ref "U19") (pin "C3") (pinfunction "PGND_C3") (pintype "power_in"))
      (node (ref "U19") (pin "C4") (pinfunction "AGND_C4") (pintype "power_in"))
      (node (ref "U19") (pin "D3") (pinfunction "PGND_D3") (pintype "power_in"))
      (node (ref "U19") (pin "E3") (pinfunction "PGND_E3") (pintype "power_in"))
      (node (ref "U19") (pin "F3") (pinfunction "PGND_F3") (pintype "power_in"))
      (node (ref "U20") (pin "11") (pinfunction "EP_11") (pintype "power_in"))
      (node (ref "U20") (pin "4") (pinfunction "PGND_4") (pintype "power_in"))
      (node (ref "U20") (pin "8") (pinfunction "GND_8") (pintype "power_in"))
      (node (ref "U21") (pin "A3") (pinfunction "PGND_A3") (pintype "power_in"))
      (node (ref "U21") (pin "B3") (pinfunction "PGND_B3") (pintype "power_in"))
      (node (ref "U21") (pin "C3") (pinfunction "PGND_C3") (pintype "power_in"))
      (node (ref "U21") (pin "C4") (pinfunction "AGND_C4") (pintype "power_in"))
      (node (ref "U21") (pin "D3") (pinfunction "PGND_D3") (pintype "power_in"))
      (node (ref "U21") (pin "E3") (pinfunction "PGND_E3") (pintype "power_in"))
      (node (ref "U21") (pin "F3") (pinfunction "PGND_F3") (pintype "power_in"))
    )
    (net (code "21") (name "Net-(L1-Pad1)") (class "Default")
      (node (ref "L1") (pin "1") (pinfunction "1_1") (pintype "passive"))
      (node (ref "U16") (pin "A2") (pinfunction "SW1_A2") (pintype "passive"))
      (node (ref "U16") (pin "B2") (pinfunction "SW1_B2") (pintype "passive"))
      (node (ref "U16") (pin "C2") (pinfunction "SW1_C2") (pintype "passive"))
    )
    (net (code "22") (name "Net-(L2-Pad1)") (class "Default")
      (node (ref "L2") (pin "1") (pinfunction "1_1") (pintype "passive"))
      (node (ref "U16") (pin "D2") (pinfunction "SW2_D2") (pintype "passive"))
      (node (ref "U16") (pin "E2") (pinfunction "SW2_E2") (pintype "passive"))
      (node (ref "U16") (pin "F2") (pinfunction "SW2_F2") (pintype "passive"))
    )
    (net (code "23") (name "Net-(L3-Pad1)") (class "Default")
      (node (ref "L3") (pin "1") (pinfunction "1_1") (pintype "passive"))
      (node (ref "U17") (pin "A2") (pinfunction "SW1_A2") (pintype "passive"))
      (node (ref "U17") (pin "B2") (pinfunction "SW1_B2") (pintype "passive"))
      (node (ref "U17") (pin "C2") (pinfunction "SW1_C2") (pintype "passive"))
    )
    (net (code "24") (name "Net-(L4-Pad1)") (class "Default")
      (node (ref "L4") (pin "1") (pinfunction "1_1") (pintype "passive"))
      (node (ref "U17") (pin "D2") (pinfunction "SW2_D2") (pintype "passive"))
      (node (ref "U17") (pin "E2") (pinfunction "SW2_E2") (pintype "passive"))
      (node (ref "U17") (pin "F2") (pinfunction "SW2_F2") (pintype "passive"))
    )
    (net (code "25") (name "Net-(L5-Pad1)") (class "Default")
      (node (ref "L5") (pin "1") (pinfunction "1_1") (pintype "passive"))
      (node (ref "U19") (pin "A2") (pinfunction "SW1_A2") (pintype "passive"))
      (node (ref "U19") (pin "B2") (pinfunction "SW1_B2") (pintype "passive"))
      (node (ref "U19") (pin "C2") (pinfunction "SW1_C2") (pintype "passive"))
    )
    (net (code "26") (name "Net-(L6-Pad1)") (class "Default")
      (node (ref "L6") (pin "1") (pinfunction "1_1") (pintype "passive"))
      (node (ref "U19") (pin "D2") (pinfunction "SW2_D2") (pintype "passive"))
      (node (ref "U19") (pin "E2") (pinfunction "SW2_E2") (pintype "passive"))
      (node (ref "U19") (pin "F2") (pinfunction "SW2_F2") (pintype "passive"))
    )
    (net (code "27") (name "Net-(L7-Pad1)") (class "Default")
      (node (ref "L7") (pin "1") (pinfunction "1_1") (pintype "passive"))
      (node (ref "U21") (pin "A2") (pinfunction "SW1_A2") (pintype "passive"))
      (node (ref "U21") (pin "B2") (pinfunction "SW1_B2") (pintype "passive"))
      (node (ref "U21") (pin "C2") (pinfunction "SW1_C2") (pintype "passive"))
    )
    (net (code "28") (name "Net-(L8-Pad1)") (class "Default")
      (node (ref "L8") (pin "1") (pinfunction "1_1") (pintype "passive"))
      (node (ref "U21") (pin "D2") (pinfunction "SW2_D2") (pintype "passive"))
      (node (ref "U21") (pin "E2") (pinfunction "SW2_E2") (pintype "passive"))
      (node (ref "U21") (pin "F2") (pinfunction "SW2_F2") (pintype "passive"))
    )
    (net (code "29") (name "Net-(U15-FB)") (class "Default")
      (node (ref "R95") (pin "1") (pinfunction "1_1") (pintype "passive"))
      (node (ref "R96") (pin "1") (pinfunction "1_1") (pintype "passive"))
      (node (ref "U15") (pin "2") (pinfunction "VOUT_2") (pintype "passive"))
      (node (ref "U15") (pin "4") (pinfunction "FB_4") (pintype "passive"))
    )
    (net (code "30") (name "Net-(U16-FB)") (class "Default")
      (node (ref "R98") (pin "1") (pinfunction "1_1") (pintype "passive"))
      (node (ref "R99") (pin "2") (pinfunction "2_2") (pintype "passive"))
      (node (ref "U16") (pin "B4") (pinfunction "FB_B4") (pintype "output"))
    )
    (net (code "31") (name "Net-(U16-SS{slash}TR)") (class "Default")
      (node (ref "C124") (pin "2") (pinfunction "2_2") (pintype "passive"))
      (node (ref "U16") (pin "D4") (pinfunction "SS/TR_D4") (pintype "passive"))
    )
    (net (code "32") (name "Net-(U17-FB)") (class "Default")
      (node (ref "R101") (pin "1") (pinfunction "1_1") (pintype "passive"))
      (node (ref "R102") (pin "2") (pinfunction "2_2") (pintype "passive"))
      (node (ref "U17") (pin "B4") (pinfunction "FB_B4") (pintype "output"))
    )
    (net (code "33") (name "Net-(U17-SS{slash}TR)") (class "Default")
      (node (ref "C129") (pin "2") (pinfunction "2_2") (pintype "passive"))
      (node (ref "U17") (pin "D4") (pinfunction "SS/TR_D4") (pintype "passive"))
    )
    (net (code "34") (name "Net-(U18-VLDOIN)") (class "Default")
      (node (ref "C135") (pin "2") (pinfunction "2_2") (pintype "passive"))
      (node (ref "R106") (pin "1") (pinfunction "1_1") (pintype "passive"))
      (node (ref "R107") (pin "2") (pinfunction "2_2") (pintype "passive"))
      (node (ref "U18") (pin "2") (pinfunction "VLDOIN_2") (pintype "passive"))
    )
    (net (code "35") (name "Net-(U19-FB)") (class "Default")
      (node (ref "R104") (pin "1") (pinfunction "1_1") (pintype "passive"))
      (node (ref "R105") (pin "2") (pinfunction "2_2") (pintype "passive"))
      (node (ref "U19") (pin "B4") (pinfunction "FB_B4") (pintype "output"))
    )
    (net (code "36") (name "Net-(U19-SS{slash}TR)") (class "Default")
      (node (ref "C134") (pin "2") (pinfunction "2_2") (pintype "passive"))
      (node (ref "U19") (pin "D4") (pinfunction "SS/TR_D4") (pintype "passive"))
    )
    (net (code "37") (name "Net-(U20-VLDOIN)") (class "Default")
      (node (ref "C150") (pin "2") (pinfunction "2_2") (pintype "passive"))
      (node (ref "R110") (pin "1") (pinfunction "1_1") (pintype "passive"))
      (node (ref "R112") (pin "2") (pinfunction "2_2") (pintype "passive"))
      (node (ref "U20") (pin "2") (pinfunction "VLDOIN_2") (pintype "passive"))
    )
    (net (code "38") (name "Net-(U21-FB)") (class "Default")
      (node (ref "R109") (pin "1") (pinfunction "1_1") (pintype "passive"))
      (node (ref "R111") (pin "2") (pinfunction "2_2") (pintype "passive"))
      (node (ref "U21") (pin "B4") (pinfunction "FB_B4") (pintype "output"))
    )
    (net (code "39") (name "Net-(U21-SS{slash}TR)") (class "Default")
      (node (ref "C149") (pin "2") (pinfunction "2_2") (pintype "passive"))
      (node (ref "U21") (pin "D4") (pinfunction "SS/TR_D4") (pintype "passive"))
    )
    (net (code "40") (name "VCCO_PL_DDR") (class "Default")
      (node (ref "C152") (pin "2") (pinfunction "2_2") (pintype "passive"))
      (node (ref "C153") (pin "2") (pinfunction "2_2") (pintype "passive"))
      (node (ref "R110") (pin "2") (pinfunction "2_2") (pintype "passive"))
      (node (ref "U20") (pin "1") (pinfunction "REFIN_1") (pintype "passive"))
    )
    (net (code "41") (name "VCCO_PS_DDR") (class "Default")
      (node (ref "C137") (pin "2") (pinfunction "2_2") (pintype "passive"))
      (node (ref "C138") (pin "2") (pinfunction "2_2") (pintype "passive"))
      (node (ref "R106") (pin "2") (pinfunction "2_2") (pintype "passive"))
      (node (ref "U18") (pin "1") (pinfunction "REFIN_1") (pintype "passive"))
    )
    (net (code "42") (name "VIN") (class "Default")
      (node (ref "C119") (pin "1") (pinfunction "1_1") (pintype "passive"))
      (node (ref "C122") (pin "2") (pinfunction "2_2") (pintype "passive"))
      (node (ref "C123") (pin "1") (pinfunction "1_1") (pintype "passive"))
      (node (ref "C125") (pin "1") (pinfunction "1_1") (pintype "passive"))
      (node (ref "C128") (pin "1") (pinfunction "1_1") (pintype "passive"))
      (node (ref "C130") (pin "1") (pinfunction "1_1") (pintype "passive"))
      (node (ref "C133") (pin "1") (pinfunction "1_1") (pintype "passive"))
      (node (ref "C145") (pin "1") (pinfunction "1_1") (pintype "passive"))
      (node (ref "C148") (pin "1") (pinfunction "1_1") (pintype "passive"))
      (node (ref "U15") (pin "1") (pinfunction "VIN_1") (pintype "passive"))
      (node (ref "U15") (pin "5") (pinfunction "EN_5") (pintype "passive"))
      (node (ref "U16") (pin "A1") (pinfunction "VIN1_A1") (pintype "power_in"))
      (node (ref "U16") (pin "B1") (pinfunction "VIN1_B1") (pintype "power_in"))
      (node (ref "U16") (pin "C1") (pinfunction "VIN1_C1") (pintype "power_in"))
      (node (ref "U16") (pin "D1") (pinfunction "VIN2_D1") (pintype "power_in"))
      (node (ref "U16") (pin "E1") (pinfunction "VIN2_E1") (pintype "power_in"))
      (node (ref "U16") (pin "F1") (pinfunction "VIN2_F1") (pintype "power_in"))
      (node (ref "U17") (pin "A1") (pinfunction "VIN1_A1") (pintype "power_in"))
      (node (ref "U17") (pin "B1") (pinfunction "VIN1_B1") (pintype "power_in"))
      (node (ref "U17") (pin "C1") (pinfunction "VIN1_C1") (pintype "power_in"))
      (node (ref "U17") (pin "D1") (pinfunction "VIN2_D1") (pintype "power_in"))
      (node (ref "U17") (pin "E1") (pinfunction "VIN2_E1") (pintype "power_in"))
      (node (ref "U17") (pin "F1") (pinfunction "VIN2_F1") (pintype "power_in"))
      (node (ref "U19") (pin "A1") (pinfunction "VIN1_A1") (pintype "power_in"))
      (node (ref "U19") (pin "B1") (pinfunction "VIN1_B1") (pintype "power_in"))
      (node (ref "U19") (pin "C1") (pinfunction "VIN1_C1") (pintype "power_in"))
      (node (ref "U19") (pin "D1") (pinfunction "VIN2_D1") (pintype "power_in"))
      (node (ref "U19") (pin "E1") (pinfunction "VIN2_E1") (pintype "power_in"))
      (node (ref "U19") (pin "F1") (pinfunction "VIN2_F1") (pintype "power_in"))
      (node (ref "U21") (pin "A1") (pinfunction "VIN1_A1") (pintype "power_in"))
      (node (ref "U21") (pin "B1") (pinfunction "VIN1_B1") (pintype "power_in"))
      (node (ref "U21") (pin "C1") (pinfunction "VIN1_C1") (pintype "power_in"))
      (node (ref "U21") (pin "D1") (pinfunction "VIN2_D1") (pintype "power_in"))
      (node (ref "U21") (pin "E1") (pinfunction "VIN2_E1") (pintype "power_in"))
      (node (ref "U21") (pin "F1") (pinfunction "VIN2_F1") (pintype "power_in"))
    )
    (net (code "43") (name "VTT_PL_DDR") (class "Default")
      (node (ref "C154") (pin "2") (pinfunction "2_2") (pintype "passive"))
      (node (ref "C155") (pin "2") (pinfunction "2_2") (pintype "passive"))
      (node (ref "C156") (pin "2") (pinfunction "2_2") (pintype "passive"))
      (node (ref "U20") (pin "3") (pinfunction "VO_3") (pintype "passive"))
      (node (ref "U20") (pin "5") (pinfunction "VOSNS_5") (pintype "passive"))
    )
    (net (code "44") (name "VTT_PL_REF") (class "Default")
      (node (ref "C157") (pin "2") (pinfunction "2_2") (pintype "passive"))
      (node (ref "U20") (pin "6") (pinfunction "REFOUT_6") (pintype "passive"))
    )
    (net (code "45") (name "VTT_PS_DDR") (class "Default")
      (node (ref "C139") (pin "2") (pinfunction "2_2") (pintype "passive"))
      (node (ref "C140") (pin "2") (pinfunction "2_2") (pintype "passive"))
      (node (ref "C141") (pin "2") (pinfunction "2_2") (pintype "passive"))
      (node (ref "U18") (pin "3") (pinfunction "VO_3") (pintype "passive"))
      (node (ref "U18") (pin "5") (pinfunction "VOSNS_5") (pintype "passive"))
    )
    (net (code "46") (name "VTT_PS_REF") (class "Default")
      (node (ref "C142") (pin "2") (pinfunction "2_2") (pintype "passive"))
      (node (ref "U18") (pin "6") (pinfunction "REFOUT_6") (pintype "passive"))
    )
  )
)
